# PWR_LMR33630_5v_3A.net
KiCad netlist of a schematic drawn in Altium Designer
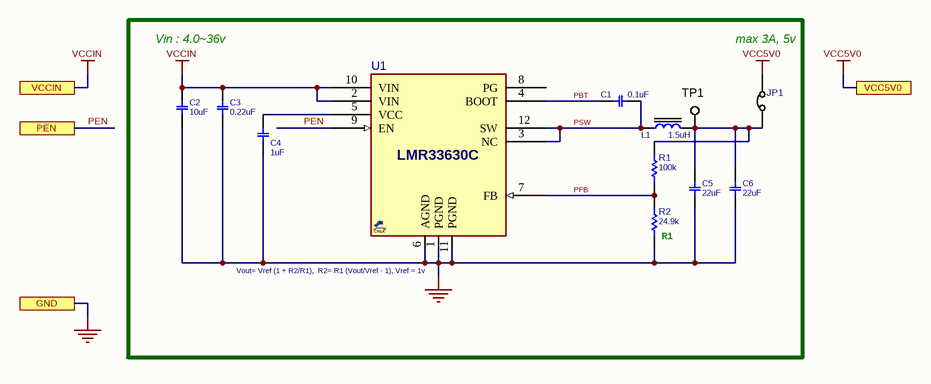
[diagram p0: PWR_LMR33630_5v_3A.SchDoc]

(export (version "E")
  (design (tool "Eeschema 10.0.6"))
  (components
    (comp (ref "C1")
      (value "0.1uF")
      (footprint "C0402")
      (description "CAP, MLCC, 100nF, 50V, X7R, 10%, 0402C")
      (fields (field (name "MANF") "Murata") (field (name "MANF_P#") "GRM155R61E104"))
      (libsource (lib "passive_mlcc_smd") (part "CAP_SMD_MLCC_100n50V"))
    )
    (comp (ref "C2")
      (value "10uF")
      (footprint "C0402")
      (description "CAP, MLCC")
      (fields (field (name "MANF_P#") "CL05A106MP5NUNC") (field (name "MANF") "Samsung"))
      (libsource (lib "passive_smd") (part "CAP_SMD_MLCC"))
    )
    (comp (ref "C3")
      (value "0.22uF")
      (footprint "C0402")
      (description "CAP, MLCC, 0402C")
      (libsource (lib "passive_mlcc_smd") (part "CAP_SMD_MLCC_100n50V"))
    )
    (comp (ref "C4")
      (value "1uF")
      (footprint "C0402")
      (description "CAP, MLCC")
      (fields (field (name "MANF_P#") "CL05A105KO5NNND") (field (name "MANF") "Samsung"))
      (libsource (lib "passive_smd") (part "CAP_SMD_MLCC"))
    )
    (comp (ref "C5")
      (value "22uF")
      (footprint "C0402")
      (description "CAP, MLCC")
      (fields (field (name "MANF_P#") "GRM158R61A226ME15") (field (name "MANF") "Murata"))
      (libsource (lib "passive_smd") (part "CAP_SMD_MLCC"))
    )
    (comp (ref "C6")
      (value "22uF")
      (footprint "C0402")
      (description "CAP, MLCC")
      (fields (field (name "MANF_P#") "GRM158R61A226ME15") (field (name "MANF") "Murata"))
      (libsource (lib "passive_smd") (part "CAP_SMD_MLCC"))
    )
    (comp (ref "JP1")
      (value "R0Ohm")
      (footprint "JP_100X60")
      (description "JUMPER, HEADER 2PIN")
      (libsource (lib "test-tp_jumper") (part "JUMPER_HDR_2P"))
    )
    (comp (ref "L1")
      (value "1.5uH")
      (footprint "L1210")
      (description "INDUCTOR")
      (fields (field (name "MANF") "Bourns") (field (name "MANF_P#") "SRP3212A-1R5M"))
      (libsource (lib "chila_passive") (part "IND_SMD_2.2uH_4A"))
    )
    (comp (ref "R1")
      (value "100k")
      (footprint "R0402")
      (description "RESISTOR, SMD, 20K, 0402")
      (libsource (lib "chila_passive") (part "RES_SMD"))
    )
    (comp (ref "R2")
      (value "24.9k")
      (footprint "R0402")
      (description "RESISTOR, SMD, 20K, 0402")
      (libsource (lib "chila_passive") (part "RES_SMD"))
    )
    (comp (ref "TP1")
      (value "TESTPOINT_SMD")
      (footprint "TPSMD_S1")
      (description "TEST POINT")
      (fields (field (name "MANF") "MANF") (field (name "MANF_P#") "MANF_P#"))
      (libsource (lib "test-tp_jumper") (part "TESTPOINT_SMD"))
    )
    (comp (ref "U1")
      (value "LMR33630C")
      (footprint "QFNHR_12_RNX")
      (description "REG, Switching, Buck, 3A, ADJ, 2.1MHz, 3.8~36VIN, QFN12")
      (fields (field (name "MANF") "Texas Instruments") (field (name "MANF_P#") "LMR33630CRNX"))
      (libsource (lib "pwr_switching_buck_hv") (part "VREG_LMR33630C_VQFNHR12"))
    )
  )
  (nets
    (net (code "1") (name "/PBT") (class "Default")
      (node (ref "C1") (pin "1") (pinfunction "1_1") (pintype "passive"))
      (node (ref "U1") (pin "4") (pinfunction "BOOT_4") (pintype "passive"))
    )
    (net (code "2") (name "/PEN") (class "Default")
      (node (ref "U1") (pin "9") (pinfunction "EN_9") (pintype "input"))
    )
    (net (code "3") (name "/PFB") (class "Default")
      (node (ref "R1") (pin "2") (pinfunction "2_2") (pintype "passive"))
      (node (ref "R2") (pin "1") (pinfunction "1_1") (pintype "passive"))
      (node (ref "U1") (pin "7") (pinfunction "FB_7") (pintype "input"))
    )
    (net (code "4") (name "/PSW") (class "Default")
      (node (ref "C1") (pin "2") (pinfunction "2_2") (pintype "passive"))
      (node (ref "L1") (pin "1") (pinfunction "1_1") (pintype "passive"))
      (node (ref "U1") (pin "12") (pinfunction "SW_12") (pintype "power_in"))
      (node (ref "U1") (pin "3") (pinfunction "NC_3") (pintype "passive"))
    )
    (net (code "5") (name "GND") (class "Default")
      (node (ref "C2") (pin "1") (pinfunction "1_1") (pintype "passive"))
      (node (ref "C3") (pin "2") (pinfunction "2_2") (pintype "passive"))
      (node (ref "C4") (pin "1") (pinfunction "1_1") (pintype "passive"))
      (node (ref "C5") (pin "1") (pinfunction "1_1") (pintype "passive"))
      (node (ref "C6") (pin "1") (pinfunction "1_1") (pintype "passive"))
      (node (ref "R2") (pin "2") (pinfunction "2_2") (pintype "passive"))
      (node (ref "U1") (pin "1") (pinfunction "PGND_1") (pintype "power_in"))
      (node (ref "U1") (pin "11") (pinfunction "PGND_11") (pintype "power_in"))
      (node (ref "U1") (pin "6") (pinfunction "AGND_6") (pintype "power_in"))
    )
    (net (code "6") (name "Net-(C5-Pad2)") (class "Default")
      (node (ref "C5") (pin "2") (pinfunction "2_2") (pintype "passive"))
      (node (ref "C6") (pin "2") (pinfunction "2_2") (pintype "passive"))
      (node (ref "JP1") (pin "1") (pinfunction "1_1") (pintype "passive"))
      (node (ref "L1") (pin "2") (pinfunction "2_2") (pintype "passive"))
      (node (ref "R1") (pin "1") (pinfunction "1_1") (pintype "passive"))
      (node (ref "TP1") (pin "1") (pinfunction "1_1") (pintype "passive"))
    )
    (net (code "7") (name "Net-(U1-VCC)") (class "Default")
      (node (ref "C4") (pin "2") (pinfunction "2_2") (pintype "passive"))
      (node (ref "U1") (pin "5") (pinfunction "VCC_5") (pintype "power_in"))
    )
    (net (code "8") (name "VCC5V0") (class "Default")
      (node (ref "JP1") (pin "2") (pinfunction "2_2") (pintype "passive"))
    )
    (net (code "9") (name "VCCIN") (class "Default")
      (node (ref "C2") (pin "2") (pinfunction "2_2") (pintype "passive"))
      (node (ref "C3") (pin "1") (pinfunction "1_1") (pintype "passive"))
      (node (ref "U1") (pin "10") (pinfunction "VIN_10") (pintype "power_in"))
      (node (ref "U1") (pin "2") (pinfunction "VIN_2") (pintype "power_in"))
    )
    (net (code "10") (name "unconnected-(U1-PG-Pad8)") (class "Default")
      (node (ref "U1") (pin "8") (pinfunction "PG_8") (pintype "open_collector"))
    )
  )
)
